# design.net
KiCad netlist of a schematic drawn in EasyEDA Pro
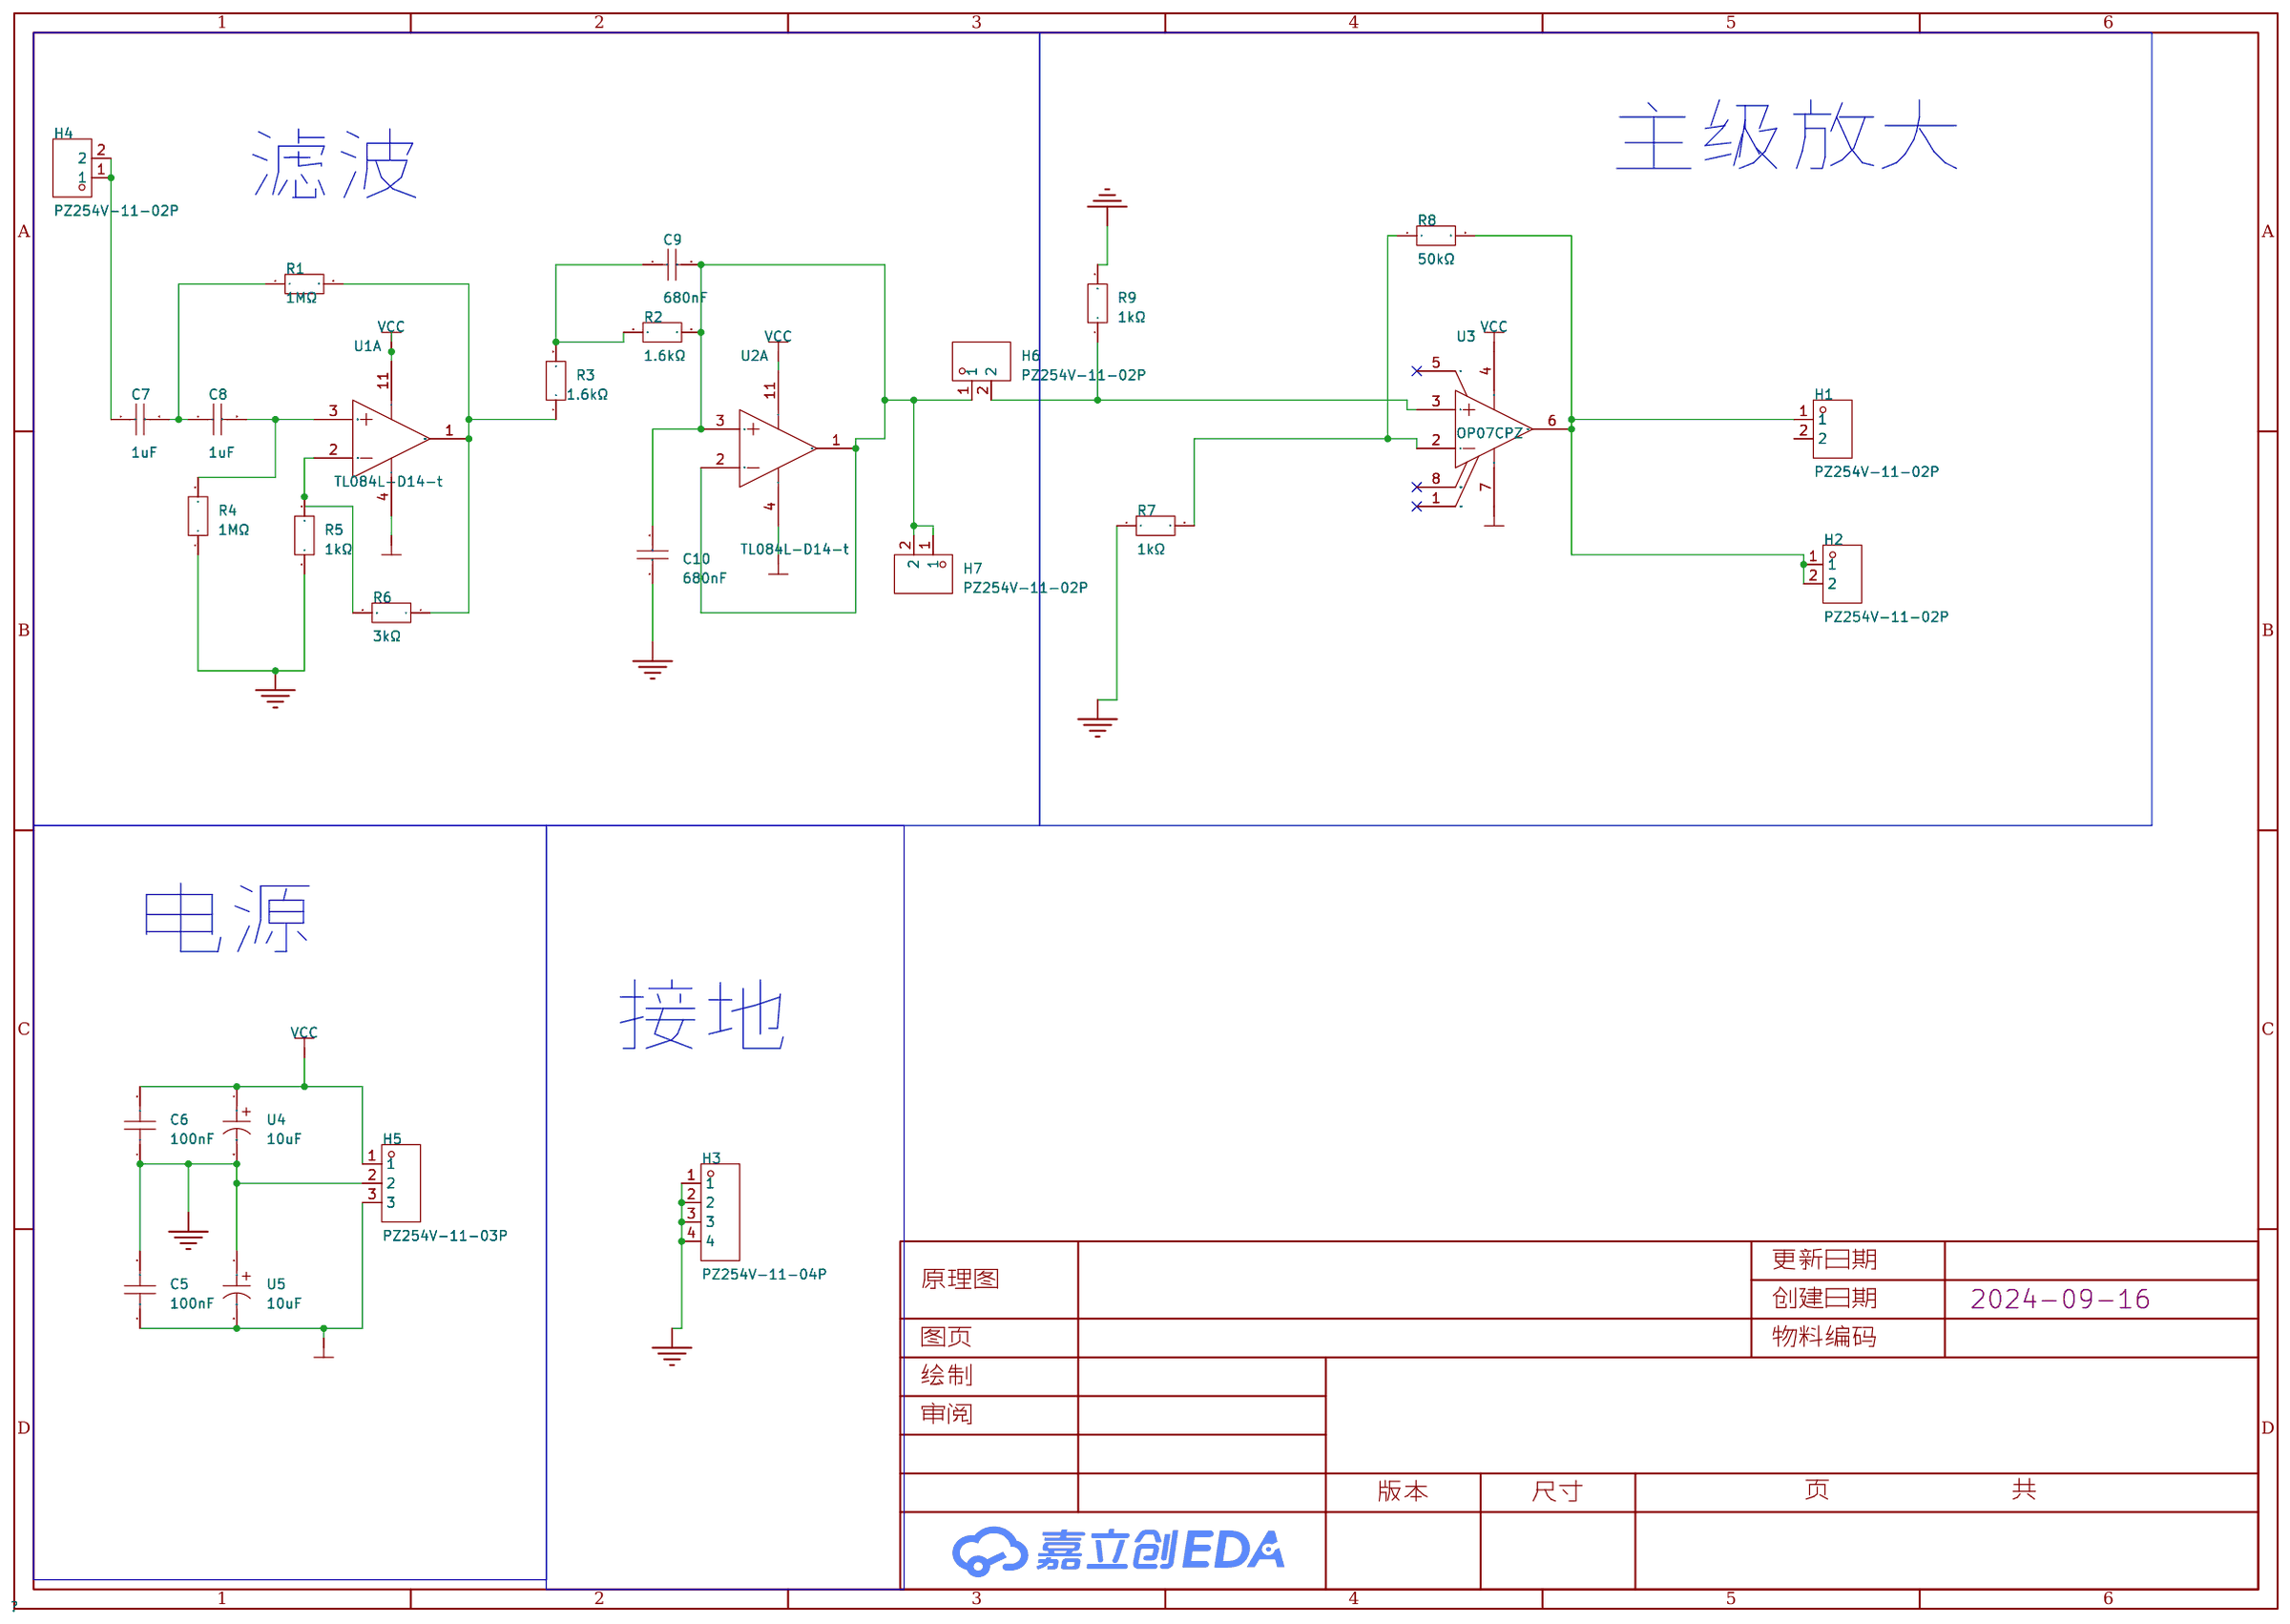
[diagram p0: schematic sheet]

(export (version "E")
  (design (tool "Eeschema 10.0.6"))
  (components
    (comp (ref "C5")
      (value "100nF")
      (footprint "easyedapro:CAP-TH_L8.5-W5.0-P5.00-D1.2")
      (description "容值:100nF;精度:±10%;额定电压:50V;温度系数:X7R;")
      (fields (field (name "Manufacturer Part") "CT4-0805B104K500F3") (field (name "Manufacturer") "FH(风华)"))
      (libsource (lib "easyedapro") (part "CT4-0805B104K500F3"))
    )
    (comp (ref "C6")
      (value "100nF")
      (footprint "easyedapro:CAP-TH_L8.5-W5.0-P5.00-D1.2")
      (description "容值:100nF;精度:±10%;额定电压:50V;温度系数:X7R;")
      (fields (field (name "Manufacturer Part") "CT4-0805B104K500F3") (field (name "Manufacturer") "FH(风华)"))
      (libsource (lib "easyedapro") (part "CT4-0805B104K500F3"))
    )
    (comp (ref "C7")
      (value "1uF")
      (footprint "easyedapro:CAP-TH_L7.5-W6.5-P5.00-D0.5")
      (description "容值:680nF;精度:±5%;额定电压:100V;工作温度:-40°C~+110°C;")
      (fields (field (name "Manufacturer Part") "PE684J2A0502") (field (name "Manufacturer") "KYET(科雅)"))
      (libsource (lib "easyedapro") (part "PE684J2A0502"))
    )
    (comp (ref "C8")
      (value "1uF")
      (footprint "easyedapro:CAP-TH_L7.5-W6.5-P5.00-D0.5")
      (description "容值:680nF;精度:±5%;额定电压:100V;工作温度:-40°C~+110°C;")
      (fields (field (name "Manufacturer Part") "PE684J2A0502") (field (name "Manufacturer") "KYET(科雅)"))
      (libsource (lib "easyedapro") (part "PE684J2A0502"))
    )
    (comp (ref "C9")
      (value "680nF")
      (footprint "easyedapro:CAP-TH_L7.5-W6.5-P5.00-D0.5")
      (description "容值:680nF;精度:±5%;额定电压:100V;工作温度:-40°C~+110°C;")
      (fields (field (name "Manufacturer Part") "PE684J2A0502") (field (name "Manufacturer") "KYET(科雅)"))
      (libsource (lib "easyedapro") (part "PE684J2A0502"))
    )
    (comp (ref "C10")
      (value "680nF")
      (footprint "easyedapro:CAP-TH_L7.5-W6.5-P5.00-D0.5")
      (description "容值:680nF;精度:±5%;额定电压:100V;工作温度:-40°C~+110°C;")
      (fields (field (name "Manufacturer Part") "PE684J2A0502") (field (name "Manufacturer") "KYET(科雅)"))
      (libsource (lib "easyedapro") (part "PE684J2A0502"))
    )
    (comp (ref "H1")
      (value "PZ254V-11-02P")
      (footprint "easyedapro:HDR-TH_2P-P2.54-V-M")
      (fields (field (name "Manufacturer") "XFCN(兴飞)"))
      (libsource (lib "easyedapro") (part "PZ254V-11-02P"))
    )
    (comp (ref "H2")
      (value "PZ254V-11-02P")
      (footprint "easyedapro:HDR-TH_2P-P2.54-V-M")
      (fields (field (name "Manufacturer") "XFCN(兴飞)"))
      (libsource (lib "easyedapro") (part "PZ254V-11-02P"))
    )
    (comp (ref "H3")
      (value "PZ254V-11-04P")
      (footprint "easyedapro:HDR-TH_4P-P2.54-V-M")
      (fields (field (name "Manufacturer") "XFCN(兴飞)"))
      (libsource (lib "easyedapro") (part "PZ254V-11-04P_C2691448"))
    )
    (comp (ref "H4")
      (value "PZ254V-11-02P")
      (footprint "easyedapro:HDR-TH_2P-P2.54-V-M")
      (fields (field (name "Manufacturer") "XFCN(兴飞)"))
      (libsource (lib "easyedapro") (part "PZ254V-11-02P"))
    )
    (comp (ref "H5")
      (value "PZ254V-11-03P")
      (footprint "easyedapro:HDR-TH_3P-P2.54-V-M")
      (fields (field (name "Manufacturer") "XFCN(兴飞)"))
      (libsource (lib "easyedapro") (part "PZ254V-11-03P_C2937625"))
    )
    (comp (ref "H6")
      (value "PZ254V-11-02P")
      (footprint "easyedapro:HDR-TH_2P-P2.54-V-M")
      (fields (field (name "Manufacturer") "XFCN(兴飞)"))
      (libsource (lib "easyedapro") (part "PZ254V-11-02P"))
    )
    (comp (ref "H7")
      (value "PZ254V-11-02P")
      (footprint "easyedapro:HDR-TH_2P-P2.54-V-M")
      (fields (field (name "Manufacturer") "XFCN(兴飞)"))
      (libsource (lib "easyedapro") (part "PZ254V-11-02P"))
    )
    (comp (ref "R1")
      (value "1MΩ")
      (footprint "easyedapro:RES-TH_BD2.4-L6.3-P10.30-D0.6")
      (description "电阻类型:金属膜电阻;阻值:10kΩ;精度:±1%;功率:250mW;温度系数:±50ppm/°C;")
      (fields
        (field (name "Manufacturer Part") "RN1/4W10KFT/BA1")
        (field (name "Manufacturer") "Tyohm(幸亚电阻)")
      )
      (libsource (lib "easyedapro") (part "RN 1/4W 10K F T/B A1"))
    )
    (comp (ref "R2")
      (value "1.6kΩ")
      (footprint "easyedapro:RES-TH_BD2.4-L6.3-P10.30-D0.6")
      (description "电阻类型:金属膜电阻;阻值:10kΩ;精度:±1%;功率:250mW;温度系数:±50ppm/°C;")
      (fields
        (field (name "Manufacturer Part") "RN1/4W10KFT/BA1")
        (field (name "Manufacturer") "Tyohm(幸亚电阻)")
      )
      (libsource (lib "easyedapro") (part "RN 1/4W 10K F T/B A1"))
    )
    (comp (ref "R3")
      (value "1.6kΩ")
      (footprint "easyedapro:RES-TH_BD2.4-L6.3-P10.30-D0.6")
      (description "电阻类型:金属膜电阻;阻值:10kΩ;精度:±1%;功率:250mW;温度系数:±50ppm/°C;")
      (fields
        (field (name "Manufacturer Part") "RN1/4W10KFT/BA1")
        (field (name "Manufacturer") "Tyohm(幸亚电阻)")
      )
      (libsource (lib "easyedapro") (part "RN 1/4W 10K F T/B A1"))
    )
    (comp (ref "R4")
      (value "1MΩ")
      (footprint "easyedapro:RES-TH_BD2.4-L6.3-P10.30-D0.6")
      (description "电阻类型:金属膜电阻;阻值:10kΩ;精度:±1%;功率:250mW;温度系数:±50ppm/°C;")
      (fields
        (field (name "Manufacturer Part") "RN1/4W10KFT/BA1")
        (field (name "Manufacturer") "Tyohm(幸亚电阻)")
      )
      (libsource (lib "easyedapro") (part "RN 1/4W 10K F T/B A1"))
    )
    (comp (ref "R5")
      (value "1kΩ")
      (footprint "easyedapro:RES-TH_BD2.4-L6.3-P10.30-D0.6")
      (description "电阻类型:金属膜电阻;阻值:10kΩ;精度:±1%;功率:250mW;温度系数:±50ppm/°C;")
      (fields
        (field (name "Manufacturer Part") "RN1/4W10KFT/BA1")
        (field (name "Manufacturer") "Tyohm(幸亚电阻)")
      )
      (libsource (lib "easyedapro") (part "RN 1/4W 10K F T/B A1"))
    )
    (comp (ref "R6")
      (value "3kΩ")
      (footprint "easyedapro:RES-TH_BD2.4-L6.3-P10.30-D0.6")
      (description "电阻类型:金属膜电阻;阻值:10kΩ;精度:±1%;功率:250mW;温度系数:±50ppm/°C;")
      (fields
        (field (name "Manufacturer Part") "RN1/4W10KFT/BA1")
        (field (name "Manufacturer") "Tyohm(幸亚电阻)")
      )
      (libsource (lib "easyedapro") (part "RN 1/4W 10K F T/B A1"))
    )
    (comp (ref "R7")
      (value "1kΩ")
      (footprint "easyedapro:RES-TH_BD2.4-L6.3-P10.30-D0.6")
      (description "电阻类型:金属膜电阻;阻值:10kΩ;精度:±1%;功率:250mW;温度系数:±50ppm/°C;")
      (fields
        (field (name "Manufacturer Part") "RN1/4W10KFT/BA1")
        (field (name "Manufacturer") "Tyohm(幸亚电阻)")
      )
      (libsource (lib "easyedapro") (part "RN 1/4W 10K F T/B A1"))
    )
    (comp (ref "R8")
      (value "50kΩ")
      (footprint "easyedapro:RES-TH_BD2.4-L6.3-P10.30-D0.6")
      (description "电阻类型:金属膜电阻;阻值:10kΩ;精度:±1%;功率:250mW;温度系数:±50ppm/°C;")
      (fields
        (field (name "Manufacturer Part") "RN1/4W10KFT/BA1")
        (field (name "Manufacturer") "Tyohm(幸亚电阻)")
      )
      (libsource (lib "easyedapro") (part "RN 1/4W 10K F T/B A1"))
    )
    (comp (ref "R9")
      (value "1kΩ")
      (footprint "easyedapro:RES-TH_BD2.4-L6.3-P10.30-D0.6")
      (description "电阻类型:金属膜电阻;阻值:10kΩ;精度:±1%;功率:250mW;温度系数:±50ppm/°C;")
      (fields
        (field (name "Manufacturer Part") "RN1/4W10KFT/BA1")
        (field (name "Manufacturer") "Tyohm(幸亚电阻)")
      )
      (libsource (lib "easyedapro") (part "RN 1/4W 10K F T/B A1"))
    )
    (comp (ref "U1")
      (value "TL084L-D14-t")
      (footprint "easyedapro:PDIP-14_L19.3-W6.5-P2.54-LS7.6-BL")
      (fields (field (name "Manufacturer") "UTC(友顺)"))
      (libsource (lib "easyedapro") (part "TL084L"))
    )
    (comp (ref "U2")
      (value "TL084L-D14-t")
      (footprint "easyedapro:PDIP-14_L19.3-W6.5-P2.54-LS7.6-BL")
      (fields (field (name "Manufacturer") "UTC(友顺)"))
      (libsource (lib "easyedapro") (part "TL084L"))
    )
    (comp (ref "U3")
      (value "OP07CPZ")
      (footprint "easyedapro:PDIP-8_L9.3-W6.4-P2.54-LS7.6-BL")
      (description "超低失调电压运算放大器")
      (fields (field (name "Manufacturer") "ADI(亚德诺)"))
      (libsource (lib "easyedapro") (part "OP07CPZ"))
    )
    (comp (ref "U4")
      (value "10uF")
      (footprint "easyedapro:CAP-TH_BD6.3-P2.50-D0.5-FD")
      (description "容值:10uF;精度:±20%;额定电压:100V;纹波电流:104mA@10kHz;等效串联电阻:-;")
      (fields
        (field (name "Manufacturer Part") "UPM2A100MED1TD")
        (field (name "Manufacturer") "Nichicon(尼吉康)")
      )
      (libsource (lib "easyedapro") (part "UPM2A100MED1TD"))
    )
    (comp (ref "U5")
      (value "10uF")
      (footprint "easyedapro:CAP-TH_BD6.3-P2.50-D0.5-FD")
      (description "容值:10uF;精度:±20%;额定电压:100V;纹波电流:104mA@10kHz;等效串联电阻:-;")
      (fields
        (field (name "Manufacturer Part") "UPM2A100MED1TD")
        (field (name "Manufacturer") "Nichicon(尼吉康)")
      )
      (libsource (lib "easyedapro") (part "UPM2A100MED1TD"))
    )
  )
  (nets
    (net (code "1") (name "GND") (class "Default")
      (node (ref "C10") (pin "1") (pinfunction "1_1") (pintype "input"))
      (node (ref "C5") (pin "2") (pinfunction "2_2") (pintype "unspecified"))
      (node (ref "C6") (pin "1") (pinfunction "1_1") (pintype "unspecified"))
      (node (ref "H3") (pin "1") (pinfunction "1_1") (pintype "unspecified"))
      (node (ref "H3") (pin "2") (pinfunction "2_2") (pintype "unspecified"))
      (node (ref "H3") (pin "3") (pinfunction "3_3") (pintype "unspecified"))
      (node (ref "H3") (pin "4") (pinfunction "4_4") (pintype "unspecified"))
      (node (ref "H5") (pin "2") (pinfunction "2_2") (pintype "unspecified"))
      (node (ref "R4") (pin "1") (pinfunction "1_1") (pintype "unspecified"))
      (node (ref "R5") (pin "1") (pinfunction "1_1") (pintype "unspecified"))
      (node (ref "R7") (pin "1") (pinfunction "1_1") (pintype "unspecified"))
      (node (ref "R9") (pin "2") (pinfunction "2_2") (pintype "unspecified"))
      (node (ref "U4") (pin "2") (pinfunction "2_2") (pintype "input"))
      (node (ref "U5") (pin "1") (pinfunction "1_1") (pintype "input"))
    )
    (net (code "2") (name "Net-(C7-Pad1)") (class "Default")
      (node (ref "C7") (pin "1") (pinfunction "1_1") (pintype "input"))
      (node (ref "H4") (pin "1") (pinfunction "1_1") (pintype "unspecified"))
      (node (ref "H4") (pin "2") (pinfunction "2_2") (pintype "unspecified"))
    )
    (net (code "3") (name "Net-(C7-Pad2)") (class "Default")
      (node (ref "C7") (pin "2") (pinfunction "2_2") (pintype "input"))
      (node (ref "C8") (pin "1") (pinfunction "1_1") (pintype "input"))
      (node (ref "R1") (pin "1") (pinfunction "1_1") (pintype "unspecified"))
    )
    (net (code "4") (name "Net-(C9-Pad1)") (class "Default")
      (node (ref "C9") (pin "1") (pinfunction "1_1") (pintype "input"))
      (node (ref "R2") (pin "1") (pinfunction "1_1") (pintype "unspecified"))
      (node (ref "R3") (pin "2") (pinfunction "2_2") (pintype "unspecified"))
    )
    (net (code "5") (name "Net-(U1A-IN1+)") (class "Default")
      (node (ref "C8") (pin "2") (pinfunction "2_2") (pintype "input"))
      (node (ref "R4") (pin "2") (pinfunction "2_2") (pintype "unspecified"))
      (node (ref "U1") (pin "3") (pinfunction "IN1+_3") (pintype "unspecified"))
    )
    (net (code "6") (name "Net-(U1A-IN1-)") (class "Default")
      (node (ref "R5") (pin "2") (pinfunction "2_2") (pintype "unspecified"))
      (node (ref "R6") (pin "2") (pinfunction "2_2") (pintype "unspecified"))
      (node (ref "U1") (pin "2") (pinfunction "IN1-_2") (pintype "unspecified"))
    )
    (net (code "7") (name "Net-(U1A-OUT1)") (class "Default")
      (node (ref "R1") (pin "2") (pinfunction "2_2") (pintype "unspecified"))
      (node (ref "R3") (pin "1") (pinfunction "1_1") (pintype "unspecified"))
      (node (ref "R6") (pin "1") (pinfunction "1_1") (pintype "unspecified"))
      (node (ref "U1") (pin "1") (pinfunction "OUT1_1") (pintype "output"))
    )
    (net (code "8") (name "Net-(U2A-IN1+)") (class "Default")
      (node (ref "C10") (pin "2") (pinfunction "2_2") (pintype "input"))
      (node (ref "C9") (pin "2") (pinfunction "2_2") (pintype "input"))
      (node (ref "H6") (pin "1") (pinfunction "1_1") (pintype "unspecified"))
      (node (ref "H7") (pin "1") (pinfunction "1_1") (pintype "unspecified"))
      (node (ref "H7") (pin "2") (pinfunction "2_2") (pintype "unspecified"))
      (node (ref "R2") (pin "2") (pinfunction "2_2") (pintype "unspecified"))
      (node (ref "U2") (pin "1") (pinfunction "OUT1_1") (pintype "output"))
      (node (ref "U2") (pin "2") (pinfunction "IN1-_2") (pintype "unspecified"))
      (node (ref "U2") (pin "3") (pinfunction "IN1+_3") (pintype "unspecified"))
    )
    (net (code "9") (name "Net-(U3-IN+)") (class "Default")
      (node (ref "H6") (pin "2") (pinfunction "2_2") (pintype "unspecified"))
      (node (ref "R9") (pin "1") (pinfunction "1_1") (pintype "unspecified"))
      (node (ref "U3") (pin "3") (pinfunction "IN+_3") (pintype "unspecified"))
    )
    (net (code "10") (name "Net-(U3-IN-)") (class "Default")
      (node (ref "R7") (pin "2") (pinfunction "2_2") (pintype "unspecified"))
      (node (ref "R8") (pin "1") (pinfunction "1_1") (pintype "unspecified"))
      (node (ref "U3") (pin "2") (pinfunction "IN-_2") (pintype "unspecified"))
    )
    (net (code "11") (name "Net-(U3-OUT)") (class "Default")
      (node (ref "H1") (pin "1") (pinfunction "1_1") (pintype "unspecified"))
      (node (ref "H2") (pin "1") (pinfunction "1_1") (pintype "unspecified"))
      (node (ref "H2") (pin "2") (pinfunction "2_2") (pintype "unspecified"))
      (node (ref "R8") (pin "2") (pinfunction "2_2") (pintype "unspecified"))
      (node (ref "U3") (pin "6") (pinfunction "OUT_6") (pintype "output"))
    )
    (net (code "12") (name "VCC") (class "Default")
      (node (ref "C6") (pin "2") (pinfunction "2_2") (pintype "unspecified"))
      (node (ref "H5") (pin "1") (pinfunction "1_1") (pintype "unspecified"))
      (node (ref "U1") (pin "11") (pinfunction "V-_11") (pintype "unspecified"))
      (node (ref "U2") (pin "11") (pinfunction "V-_11") (pintype "unspecified"))
      (node (ref "U3") (pin "4") (pinfunction "V-_4") (pintype "unspecified"))
      (node (ref "U4") (pin "1") (pinfunction "1_1") (pintype "input"))
    )
    (net (code "13") (name "VDD") (class "Default")
      (node (ref "C5") (pin "1") (pinfunction "1_1") (pintype "unspecified"))
      (node (ref "H5") (pin "3") (pinfunction "3_3") (pintype "unspecified"))
      (node (ref "U1") (pin "4") (pinfunction "V+_4") (pintype "unspecified"))
      (node (ref "U2") (pin "4") (pinfunction "V+_4") (pintype "unspecified"))
      (node (ref "U3") (pin "7") (pinfunction "V+_7") (pintype "unspecified"))
      (node (ref "U5") (pin "2") (pinfunction "2_2") (pintype "input"))
    )
    (net (code "14") (name "unconnected-(H1-Pad2)") (class "Default")
      (node (ref "H1") (pin "2") (pinfunction "2_2") (pintype "unspecified"))
    )
    (net (code "15") (name "unconnected-(U3-NC-Pad5)") (class "Default")
      (node (ref "U3") (pin "5") (pinfunction "NC_5") (pintype "unspecified+no_connect"))
    )
    (net (code "16") (name "unconnected-(U3-VOS_TRIM-Pad1)") (class "Default")
      (node (ref "U3") (pin "1") (pinfunction "VOS_TRIM_1") (pintype "unspecified+no_connect"))
    )
    (net (code "17") (name "unconnected-(U3-VOS_TRIM-Pad8)") (class "Default")
      (node (ref "U3") (pin "8") (pinfunction "VOS_TRIM_8") (pintype "unspecified+no_connect"))
    )
  )
)
